# preampli.net
KiCad netlist of a schematic drawn in EAGLE
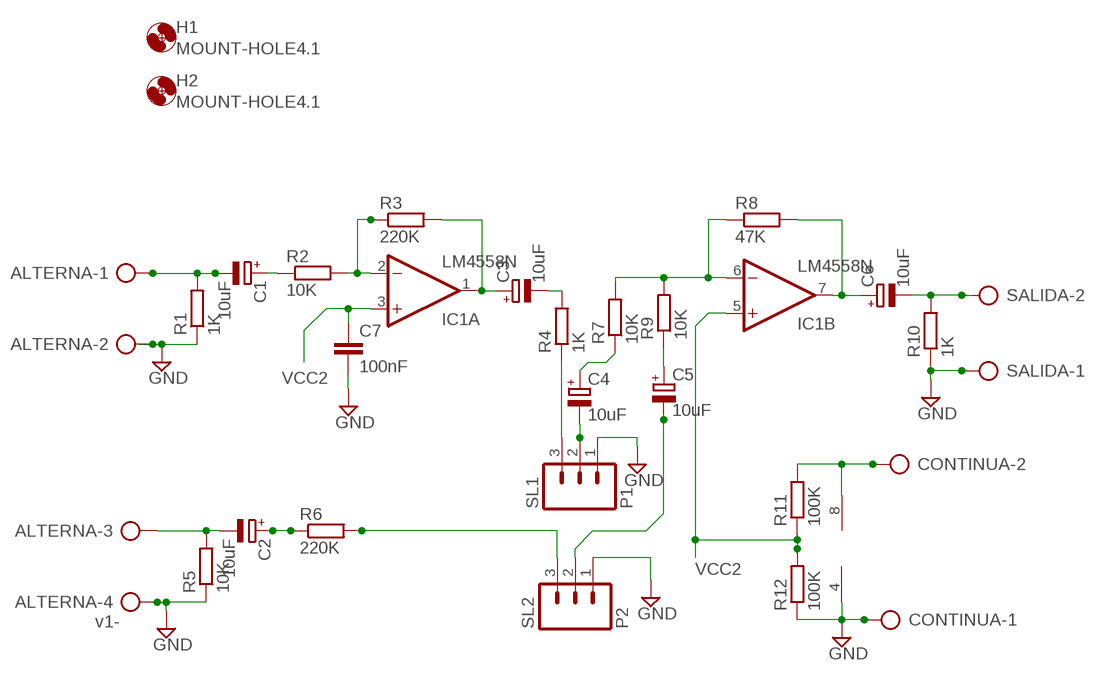
[diagram p0: schematic, sheet 1]

(export (version "E")
  (design (tool "Eeschema 10.0.6"))
  (components
    (comp (ref "ALTERNA")
      (value "v1-")
      (footprint "eagle-import:AK500_4")
      (libsource (lib "eagle-import") (part "AK500/4"))
    )
    (comp (ref "C1")
      (value "10uF")
      (footprint "eagle-import:E2,5-6E")
      (libsource (lib "eagle-import") (part "CPOL-EUE2,5-6E"))
    )
    (comp (ref "C2")
      (value "10uF")
      (footprint "eagle-import:E2,5-6E")
      (libsource (lib "eagle-import") (part "CPOL-EUE2,5-6E"))
    )
    (comp (ref "C3")
      (value "10uF")
      (footprint "eagle-import:E2,5-6E")
      (libsource (lib "eagle-import") (part "CPOL-EUE2,5-6E"))
    )
    (comp (ref "C4")
      (value "10uF")
      (footprint "eagle-import:E2,5-6E")
      (libsource (lib "eagle-import") (part "CPOL-EUE2,5-6E"))
    )
    (comp (ref "C5")
      (value "10uF")
      (footprint "eagle-import:E2,5-6E")
      (libsource (lib "eagle-import") (part "CPOL-EUE2,5-6E"))
    )
    (comp (ref "C6")
      (value "10uF")
      (footprint "eagle-import:E2,5-6E")
      (libsource (lib "eagle-import") (part "CPOL-EUE2,5-6E"))
    )
    (comp (ref "C7")
      (value "100nF")
      (footprint "eagle-import:C025-025X050")
      (libsource (lib "eagle-import") (part "C-EU025-025X050"))
    )
    (comp (ref "CONTINUA")
      (value "AK500/2")
      (footprint "eagle-import:AK500_2")
      (libsource (lib "eagle-import") (part "AK500/2"))
    )
    (comp (ref "H1")
      (value "MOUNT-HOLE4.1")
      (footprint "eagle-import:4,1")
      (libsource (lib "eagle-import") (part "MOUNT-HOLE4.1"))
    )
    (comp (ref "H2")
      (value "MOUNT-HOLE4.1")
      (footprint "eagle-import:4,1")
      (libsource (lib "eagle-import") (part "MOUNT-HOLE4.1"))
    )
    (comp (ref "IC1")
      (value "LM4558N")
      (footprint "eagle-import:DIL08")
      (libsource (lib "eagle-import") (part "4558NLM"))
    )
    (comp (ref "R1")
      (value "1K")
      (footprint "eagle-import:0207_10")
      (libsource (lib "eagle-import") (part "R-EU_0207/10"))
    )
    (comp (ref "R2")
      (value "10K")
      (footprint "eagle-import:0207_10")
      (libsource (lib "eagle-import") (part "R-EU_0207/10"))
    )
    (comp (ref "R3")
      (value "220K")
      (footprint "eagle-import:0207_10")
      (libsource (lib "eagle-import") (part "R-EU_0207/10"))
    )
    (comp (ref "R4")
      (value "1K")
      (footprint "eagle-import:0207_10")
      (libsource (lib "eagle-import") (part "R-EU_0207/10"))
    )
    (comp (ref "R5")
      (value "10K")
      (footprint "eagle-import:0207_10")
      (libsource (lib "eagle-import") (part "R-EU_0207/10"))
    )
    (comp (ref "R6")
      (value "220K")
      (footprint "eagle-import:0207_10")
      (libsource (lib "eagle-import") (part "R-EU_0207/10"))
    )
    (comp (ref "R7")
      (value "10K")
      (footprint "eagle-import:0207_10")
      (libsource (lib "eagle-import") (part "R-EU_0207/10"))
    )
    (comp (ref "R8")
      (value "47K")
      (footprint "eagle-import:0207_10")
      (libsource (lib "eagle-import") (part "R-EU_0207/10"))
    )
    (comp (ref "R9")
      (value "10K")
      (footprint "eagle-import:0207_10")
      (libsource (lib "eagle-import") (part "R-EU_0207/10"))
    )
    (comp (ref "R10")
      (value "1K")
      (footprint "eagle-import:0207_10")
      (libsource (lib "eagle-import") (part "R-EU_0207/10"))
    )
    (comp (ref "R11")
      (value "100K")
      (footprint "eagle-import:0207_10")
      (libsource (lib "eagle-import") (part "resistor_R-EU_0207/10"))
    )
    (comp (ref "R12")
      (value "100K")
      (footprint "eagle-import:0207_10")
      (libsource (lib "eagle-import") (part "resistor_R-EU_0207/10"))
    )
    (comp (ref "SALIDA")
      (value "AK500/2")
      (footprint "eagle-import:AK500_2")
      (libsource (lib "eagle-import") (part "AK500/2"))
    )
    (comp (ref "SL1")
      (value "P1")
      (footprint "eagle-import:03P")
      (libsource (lib "eagle-import") (part "MA03"))
    )
    (comp (ref "SL2")
      (value "P2")
      (footprint "eagle-import:03P")
      (libsource (lib "eagle-import") (part "MA03"))
    )
  )
  (nets
    (net (code "1") (name "/VCC2") (class "Default")
      (node (ref "C7") (pin "1") (pinfunction "1_1") (pintype "passive"))
      (node (ref "IC1") (pin "3") (pinfunction "+IN_3") (pintype "input"))
      (node (ref "IC1") (pin "5") (pinfunction "+IN_5") (pintype "input"))
      (node (ref "R11") (pin "1") (pinfunction "1_1") (pintype "passive"))
      (node (ref "R12") (pin "2") (pinfunction "2_2") (pintype "passive"))
    )
    (net (code "2") (name "GND") (class "Default")
      (node (ref "ALTERNA") (pin "2") (pinfunction "KL_2") (pintype "passive"))
      (node (ref "ALTERNA") (pin "4") (pinfunction "KL_4") (pintype "passive"))
      (node (ref "C7") (pin "2") (pinfunction "2_2") (pintype "passive"))
      (node (ref "CONTINUA") (pin "1") (pinfunction "KL_1") (pintype "passive"))
      (node (ref "IC1") (pin "4") (pinfunction "V-_4") (pintype "power_in"))
      (node (ref "R1") (pin "1") (pinfunction "1_1") (pintype "passive"))
      (node (ref "R10") (pin "1") (pinfunction "1_1") (pintype "passive"))
      (node (ref "R12") (pin "1") (pinfunction "1_1") (pintype "passive"))
      (node (ref "R5") (pin "1") (pinfunction "1_1") (pintype "passive"))
      (node (ref "SALIDA") (pin "1") (pinfunction "KL_1") (pintype "passive"))
      (node (ref "SL1") (pin "1") (pinfunction "1_1") (pintype "passive"))
      (node (ref "SL2") (pin "1") (pinfunction "1_1") (pintype "passive"))
    )
    (net (code "3") (name "Net-(ALTERNAA-KL)") (class "Default")
      (node (ref "ALTERNA") (pin "1") (pinfunction "KL_1") (pintype "passive"))
      (node (ref "C1") (pin "-") (pinfunction "-_-") (pintype "passive"))
      (node (ref "R1") (pin "2") (pinfunction "2_2") (pintype "passive"))
    )
    (net (code "4") (name "Net-(ALTERNAC-KL)") (class "Default")
      (node (ref "ALTERNA") (pin "3") (pinfunction "KL_3") (pintype "passive"))
      (node (ref "C2") (pin "-") (pinfunction "-_-") (pintype "passive"))
      (node (ref "R5") (pin "2") (pinfunction "2_2") (pintype "passive"))
    )
    (net (code "5") (name "Net-(C1-Pad+)") (class "Default")
      (node (ref "C1") (pin "+") (pinfunction "+_+") (pintype "passive"))
      (node (ref "R2") (pin "1") (pinfunction "1_1") (pintype "passive"))
    )
    (net (code "6") (name "Net-(C2-Pad+)") (class "Default")
      (node (ref "C2") (pin "+") (pinfunction "+_+") (pintype "passive"))
      (node (ref "R6") (pin "1") (pinfunction "1_1") (pintype "passive"))
    )
    (net (code "7") (name "Net-(C3-Pad-)") (class "Default")
      (node (ref "C3") (pin "-") (pinfunction "-_-") (pintype "passive"))
      (node (ref "R4") (pin "2") (pinfunction "2_2") (pintype "passive"))
    )
    (net (code "8") (name "Net-(C4-Pad+)") (class "Default")
      (node (ref "C4") (pin "+") (pinfunction "+_+") (pintype "passive"))
      (node (ref "R7") (pin "1") (pinfunction "1_1") (pintype "passive"))
    )
    (net (code "9") (name "Net-(C4-Pad-)") (class "Default")
      (node (ref "C4") (pin "-") (pinfunction "-_-") (pintype "passive"))
      (node (ref "SL1") (pin "2") (pinfunction "2_2") (pintype "passive"))
    )
    (net (code "10") (name "Net-(C5-Pad+)") (class "Default")
      (node (ref "C5") (pin "+") (pinfunction "+_+") (pintype "passive"))
      (node (ref "R9") (pin "1") (pinfunction "1_1") (pintype "passive"))
    )
    (net (code "11") (name "Net-(C5-Pad-)") (class "Default")
      (node (ref "C5") (pin "-") (pinfunction "-_-") (pintype "passive"))
      (node (ref "SL2") (pin "2") (pinfunction "2_2") (pintype "passive"))
    )
    (net (code "12") (name "Net-(CONTINUAB-KL)") (class "Default")
      (node (ref "CONTINUA") (pin "2") (pinfunction "KL_2") (pintype "passive"))
      (node (ref "IC1") (pin "8") (pinfunction "V+_8") (pintype "power_in"))
      (node (ref "R11") (pin "2") (pinfunction "2_2") (pintype "passive"))
    )
    (net (code "13") (name "Net-(IC1A--IN)") (class "Default")
      (node (ref "IC1") (pin "2") (pinfunction "-IN_2") (pintype "input"))
      (node (ref "R2") (pin "2") (pinfunction "2_2") (pintype "passive"))
      (node (ref "R3") (pin "1") (pinfunction "1_1") (pintype "passive"))
    )
    (net (code "14") (name "Net-(IC1A-OUT)") (class "Default")
      (node (ref "C3") (pin "+") (pinfunction "+_+") (pintype "passive"))
      (node (ref "IC1") (pin "1") (pinfunction "OUT_1") (pintype "output"))
      (node (ref "R3") (pin "2") (pinfunction "2_2") (pintype "passive"))
    )
    (net (code "15") (name "Net-(IC1B--IN)") (class "Default")
      (node (ref "IC1") (pin "6") (pinfunction "-IN_6") (pintype "input"))
      (node (ref "R7") (pin "2") (pinfunction "2_2") (pintype "passive"))
      (node (ref "R8") (pin "1") (pinfunction "1_1") (pintype "passive"))
      (node (ref "R9") (pin "2") (pinfunction "2_2") (pintype "passive"))
    )
    (net (code "16") (name "Net-(IC1B-OUT)") (class "Default")
      (node (ref "C6") (pin "+") (pinfunction "+_+") (pintype "passive"))
      (node (ref "IC1") (pin "7") (pinfunction "OUT_7") (pintype "output"))
      (node (ref "R8") (pin "2") (pinfunction "2_2") (pintype "passive"))
    )
    (net (code "17") (name "Net-(R4-Pad1)") (class "Default")
      (node (ref "R4") (pin "1") (pinfunction "1_1") (pintype "passive"))
      (node (ref "SL1") (pin "3") (pinfunction "3_3") (pintype "passive"))
    )
    (net (code "18") (name "Net-(R6-Pad2)") (class "Default")
      (node (ref "R6") (pin "2") (pinfunction "2_2") (pintype "passive"))
      (node (ref "SL2") (pin "3") (pinfunction "3_3") (pintype "passive"))
    )
    (net (code "19") (name "Net-(SALIDAB-KL)") (class "Default")
      (node (ref "C6") (pin "-") (pinfunction "-_-") (pintype "passive"))
      (node (ref "R10") (pin "2") (pinfunction "2_2") (pintype "passive"))
      (node (ref "SALIDA") (pin "2") (pinfunction "KL_2") (pintype "passive"))
    )
  )
)
